# MIU60_REVE.net
KiCad netlist of a schematic drawn in EAGLE
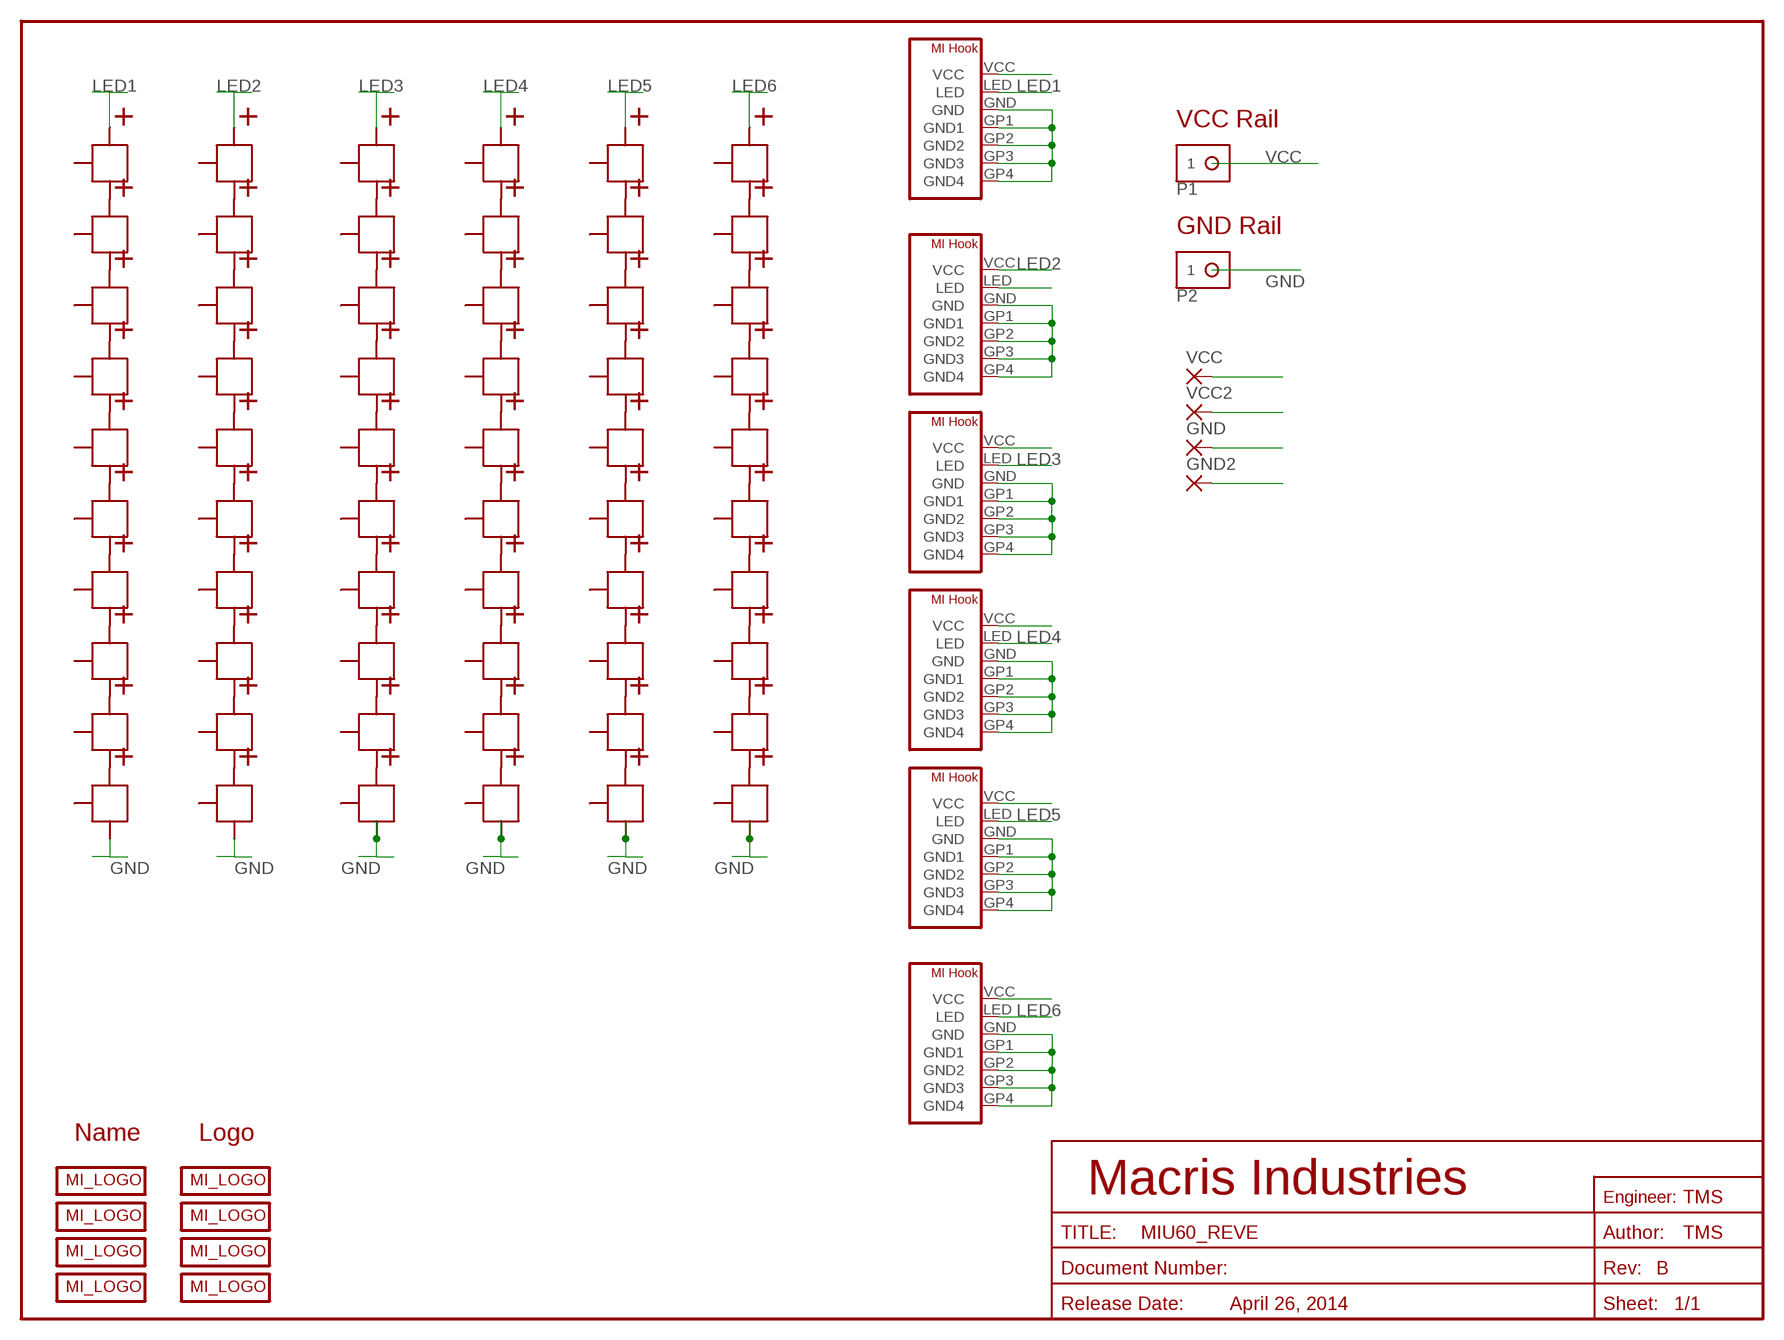
[diagram p0: schematic, sheet 1]

(export (version "E")
  (design (tool "Eeschema 10.0.6"))
  (components
    (comp (ref "GND")
      (value "SMD5")
      (footprint "eagle-import:SMD2,54-5,08")
      (libsource (lib "eagle-import") (part "SMD5"))
    )
    (comp (ref "GND2")
      (value "SMD5")
      (footprint "eagle-import:SMD2,54-5,08")
      (libsource (lib "eagle-import") (part "SMD5"))
    )
    (comp (ref "P1")
      (value "PAD-10G")
      (footprint "eagle-import:PAD_10G")
      (libsource (lib "eagle-import") (part "PAD-10G"))
    )
    (comp (ref "P2")
      (value "PAD-10G")
      (footprint "eagle-import:PAD_10G")
      (libsource (lib "eagle-import") (part "PAD-10G"))
    )
    (comp (ref "U$1")
      (value "MI_LOGO-50MIL")
      (footprint "eagle-import:MI_LOGO_NAME_2")
      (libsource (lib "eagle-import") (part "MI_LOGO-NAME_TWO"))
    )
    (comp (ref "U$2")
      (value "MI_LOGO-2014_USA")
      (footprint "eagle-import:MACRIS_USA_LOGO")
      (libsource (lib "eagle-import") (part "MI_LOGO-2014_USA"))
    )
    (comp (ref "U$3")
      (value "MI_LOGO-50MIL")
      (footprint "eagle-import:MI_LOGO_NAME_2")
      (libsource (lib "eagle-import") (part "MI_LOGO-NAME_TWO"))
    )
    (comp (ref "U$4")
      (value "MI_LOGO-2014_USA")
      (footprint "eagle-import:MACRIS_USA_LOGO")
      (libsource (lib "eagle-import") (part "MI_LOGO-2014_USA"))
    )
    (comp (ref "U$5")
      (value "MI_LOGO-50MIL")
      (footprint "eagle-import:MI_LOGO_NAME_2")
      (libsource (lib "eagle-import") (part "MI_LOGO-NAME_TWO"))
    )
    (comp (ref "U$6")
      (value "MI_LOGO-50MIL")
      (footprint "eagle-import:MI_LOGO_NAME_2")
      (libsource (lib "eagle-import") (part "MI_LOGO-NAME_TWO"))
    )
    (comp (ref "U$7")
      (value "MI_LOGO-2014_USA")
      (footprint "eagle-import:MACRIS_USA_LOGO")
      (libsource (lib "eagle-import") (part "MI_LOGO-2014_USA"))
    )
    (comp (ref "U$8")
      (value "MI_LOGO-2014_USA")
      (footprint "eagle-import:MACRIS_USA_LOGO")
      (libsource (lib "eagle-import") (part "MI_LOGO-2014_USA"))
    )
    (comp (ref "U$9")
      (value "MI_DRIVER_HOOKUP")
      (footprint "eagle-import:MI_DRIVE_HOOKUP")
      (libsource (lib "eagle-import") (part "MI_DRIVER_HOOKUP"))
    )
    (comp (ref "U$10")
      (value "MI_DRIVER_HOOKUP")
      (footprint "eagle-import:MI_DRIVE_HOOKUP")
      (libsource (lib "eagle-import") (part "MI_DRIVER_HOOKUP"))
    )
    (comp (ref "U$11")
      (value "MI_DRIVER_HOOKUP")
      (footprint "eagle-import:MI_DRIVE_HOOKUP")
      (libsource (lib "eagle-import") (part "MI_DRIVER_HOOKUP"))
    )
    (comp (ref "U$12")
      (value "MI_DRIVER_HOOKUP")
      (footprint "eagle-import:MI_DRIVE_HOOKUP")
      (libsource (lib "eagle-import") (part "MI_DRIVER_HOOKUP"))
    )
    (comp (ref "U$13")
      (value "MI_DRIVER_HOOKUP")
      (footprint "eagle-import:MI_DRIVE_HOOKUP")
      (libsource (lib "eagle-import") (part "MI_DRIVER_HOOKUP"))
    )
    (comp (ref "U$14")
      (value "MI_DRIVER_HOOKUP")
      (footprint "eagle-import:MI_DRIVE_HOOKUP")
      (libsource (lib "eagle-import") (part "MI_DRIVER_HOOKUP"))
    )
    (comp (ref "U$16")
      (value "CREE_XP")
      (footprint "eagle-import:XP")
      (libsource (lib "eagle-import") (part "CREE_XP"))
    )
    (comp (ref "U$17")
      (value "CREE_XP")
      (footprint "eagle-import:XP")
      (libsource (lib "eagle-import") (part "CREE_XP"))
    )
    (comp (ref "U$18")
      (value "CREE_XP")
      (footprint "eagle-import:XP")
      (libsource (lib "eagle-import") (part "CREE_XP"))
    )
    (comp (ref "U$19")
      (value "CREE_XP")
      (footprint "eagle-import:XP")
      (libsource (lib "eagle-import") (part "CREE_XP"))
    )
    (comp (ref "U$20")
      (value "CREE_XP")
      (footprint "eagle-import:XP")
      (libsource (lib "eagle-import") (part "CREE_XP"))
    )
    (comp (ref "U$21")
      (value "CREE_XP")
      (footprint "eagle-import:XP")
      (libsource (lib "eagle-import") (part "CREE_XP"))
    )
    (comp (ref "U$22")
      (value "CREE_XP")
      (footprint "eagle-import:XP")
      (libsource (lib "eagle-import") (part "CREE_XP"))
    )
    (comp (ref "U$23")
      (value "CREE_XP")
      (footprint "eagle-import:XP")
      (libsource (lib "eagle-import") (part "CREE_XP"))
    )
    (comp (ref "U$24")
      (value "CREE_XP")
      (footprint "eagle-import:XP")
      (libsource (lib "eagle-import") (part "CREE_XP"))
    )
    (comp (ref "U$25")
      (value "CREE_XP")
      (footprint "eagle-import:XP")
      (libsource (lib "eagle-import") (part "CREE_XP"))
    )
    (comp (ref "U$26")
      (value "CREE_XP")
      (footprint "eagle-import:XP")
      (libsource (lib "eagle-import") (part "CREE_XP"))
    )
    (comp (ref "U$27")
      (value "CREE_XP")
      (footprint "eagle-import:XP")
      (libsource (lib "eagle-import") (part "CREE_XP"))
    )
    (comp (ref "U$28")
      (value "CREE_XP")
      (footprint "eagle-import:XP")
      (libsource (lib "eagle-import") (part "CREE_XP"))
    )
    (comp (ref "U$29")
      (value "CREE_XP")
      (footprint "eagle-import:XP")
      (libsource (lib "eagle-import") (part "CREE_XP"))
    )
    (comp (ref "U$30")
      (value "CREE_XP")
      (footprint "eagle-import:XP")
      (libsource (lib "eagle-import") (part "CREE_XP"))
    )
    (comp (ref "U$31")
      (value "CREE_XP")
      (footprint "eagle-import:XP")
      (libsource (lib "eagle-import") (part "CREE_XP"))
    )
    (comp (ref "U$32")
      (value "CREE_XP")
      (footprint "eagle-import:XP")
      (libsource (lib "eagle-import") (part "CREE_XP"))
    )
    (comp (ref "U$33")
      (value "CREE_XP")
      (footprint "eagle-import:XP")
      (libsource (lib "eagle-import") (part "CREE_XP"))
    )
    (comp (ref "U$34")
      (value "CREE_XP")
      (footprint "eagle-import:XP")
      (libsource (lib "eagle-import") (part "CREE_XP"))
    )
    (comp (ref "U$35")
      (value "CREE_XP")
      (footprint "eagle-import:XP")
      (libsource (lib "eagle-import") (part "CREE_XP"))
    )
    (comp (ref "U$36")
      (value "CREE_XP")
      (footprint "eagle-import:XP")
      (libsource (lib "eagle-import") (part "CREE_XP"))
    )
    (comp (ref "U$37")
      (value "CREE_XP")
      (footprint "eagle-import:XP")
      (libsource (lib "eagle-import") (part "CREE_XP"))
    )
    (comp (ref "U$38")
      (value "CREE_XP")
      (footprint "eagle-import:XP")
      (libsource (lib "eagle-import") (part "CREE_XP"))
    )
    (comp (ref "U$39")
      (value "CREE_XP")
      (footprint "eagle-import:XP")
      (libsource (lib "eagle-import") (part "CREE_XP"))
    )
    (comp (ref "U$40")
      (value "CREE_XP")
      (footprint "eagle-import:XP")
      (libsource (lib "eagle-import") (part "CREE_XP"))
    )
    (comp (ref "U$41")
      (value "CREE_XP")
      (footprint "eagle-import:XP")
      (libsource (lib "eagle-import") (part "CREE_XP"))
    )
    (comp (ref "U$42")
      (value "CREE_XP")
      (footprint "eagle-import:XP")
      (libsource (lib "eagle-import") (part "CREE_XP"))
    )
    (comp (ref "U$43")
      (value "CREE_XP")
      (footprint "eagle-import:XP")
      (libsource (lib "eagle-import") (part "CREE_XP"))
    )
    (comp (ref "U$44")
      (value "CREE_XP")
      (footprint "eagle-import:XP")
      (libsource (lib "eagle-import") (part "CREE_XP"))
    )
    (comp (ref "U$45")
      (value "CREE_XP")
      (footprint "eagle-import:XP")
      (libsource (lib "eagle-import") (part "CREE_XP"))
    )
    (comp (ref "U$46")
      (value "CREE_XP")
      (footprint "eagle-import:XP")
      (libsource (lib "eagle-import") (part "CREE_XP"))
    )
    (comp (ref "U$47")
      (value "CREE_XP")
      (footprint "eagle-import:XP")
      (libsource (lib "eagle-import") (part "CREE_XP"))
    )
    (comp (ref "U$48")
      (value "CREE_XP")
      (footprint "eagle-import:XP")
      (libsource (lib "eagle-import") (part "CREE_XP"))
    )
    (comp (ref "U$49")
      (value "CREE_XP")
      (footprint "eagle-import:XP")
      (libsource (lib "eagle-import") (part "CREE_XP"))
    )
    (comp (ref "U$50")
      (value "CREE_XP")
      (footprint "eagle-import:XP")
      (libsource (lib "eagle-import") (part "CREE_XP"))
    )
    (comp (ref "U$51")
      (value "CREE_XP")
      (footprint "eagle-import:XP")
      (libsource (lib "eagle-import") (part "CREE_XP"))
    )
    (comp (ref "U$52")
      (value "CREE_XP")
      (footprint "eagle-import:XP")
      (libsource (lib "eagle-import") (part "CREE_XP"))
    )
    (comp (ref "U$53")
      (value "CREE_XP")
      (footprint "eagle-import:XP")
      (libsource (lib "eagle-import") (part "CREE_XP"))
    )
    (comp (ref "U$54")
      (value "CREE_XP")
      (footprint "eagle-import:XP")
      (libsource (lib "eagle-import") (part "CREE_XP"))
    )
    (comp (ref "U$55")
      (value "CREE_XP")
      (footprint "eagle-import:XP")
      (libsource (lib "eagle-import") (part "CREE_XP"))
    )
    (comp (ref "U$56")
      (value "CREE_XP")
      (footprint "eagle-import:XP")
      (libsource (lib "eagle-import") (part "CREE_XP"))
    )
    (comp (ref "U$57")
      (value "CREE_XP")
      (footprint "eagle-import:XP")
      (libsource (lib "eagle-import") (part "CREE_XP"))
    )
    (comp (ref "U$58")
      (value "CREE_XP")
      (footprint "eagle-import:XP")
      (libsource (lib "eagle-import") (part "CREE_XP"))
    )
    (comp (ref "U$59")
      (value "CREE_XP")
      (footprint "eagle-import:XP")
      (libsource (lib "eagle-import") (part "CREE_XP"))
    )
    (comp (ref "U$60")
      (value "CREE_XP")
      (footprint "eagle-import:XP")
      (libsource (lib "eagle-import") (part "CREE_XP"))
    )
    (comp (ref "U$61")
      (value "CREE_XP")
      (footprint "eagle-import:XP")
      (libsource (lib "eagle-import") (part "CREE_XP"))
    )
    (comp (ref "U$62")
      (value "CREE_XP")
      (footprint "eagle-import:XP")
      (libsource (lib "eagle-import") (part "CREE_XP"))
    )
    (comp (ref "U$63")
      (value "CREE_XP")
      (footprint "eagle-import:XP")
      (libsource (lib "eagle-import") (part "CREE_XP"))
    )
    (comp (ref "U$64")
      (value "CREE_XP")
      (footprint "eagle-import:XP")
      (libsource (lib "eagle-import") (part "CREE_XP"))
    )
    (comp (ref "U$65")
      (value "CREE_XP")
      (footprint "eagle-import:XP")
      (libsource (lib "eagle-import") (part "CREE_XP"))
    )
    (comp (ref "U$66")
      (value "CREE_XP")
      (footprint "eagle-import:XP")
      (libsource (lib "eagle-import") (part "CREE_XP"))
    )
    (comp (ref "U$67")
      (value "CREE_XP")
      (footprint "eagle-import:XP")
      (libsource (lib "eagle-import") (part "CREE_XP"))
    )
    (comp (ref "U$68")
      (value "CREE_XP")
      (footprint "eagle-import:XP")
      (libsource (lib "eagle-import") (part "CREE_XP"))
    )
    (comp (ref "U$69")
      (value "CREE_XP")
      (footprint "eagle-import:XP")
      (libsource (lib "eagle-import") (part "CREE_XP"))
    )
    (comp (ref "U$70")
      (value "CREE_XP")
      (footprint "eagle-import:XP")
      (libsource (lib "eagle-import") (part "CREE_XP"))
    )
    (comp (ref "U$71")
      (value "CREE_XP")
      (footprint "eagle-import:XP")
      (libsource (lib "eagle-import") (part "CREE_XP"))
    )
    (comp (ref "U$72")
      (value "CREE_XP")
      (footprint "eagle-import:XP")
      (libsource (lib "eagle-import") (part "CREE_XP"))
    )
    (comp (ref "U$73")
      (value "CREE_XP")
      (footprint "eagle-import:XP")
      (libsource (lib "eagle-import") (part "CREE_XP"))
    )
    (comp (ref "U$74")
      (value "CREE_XP")
      (footprint "eagle-import:XP")
      (libsource (lib "eagle-import") (part "CREE_XP"))
    )
    (comp (ref "U$75")
      (value "CREE_XP")
      (footprint "eagle-import:XP")
      (libsource (lib "eagle-import") (part "CREE_XP"))
    )
    (comp (ref "VCC")
      (value "SMD5")
      (footprint "eagle-import:SMD2,54-5,08")
      (libsource (lib "eagle-import") (part "SMD5"))
    )
    (comp (ref "VCC2")
      (value "SMD5")
      (footprint "eagle-import:SMD2,54-5,08")
      (libsource (lib "eagle-import") (part "SMD5"))
    )
  )
  (nets
    (net (code "1") (name "/GND") (class "Default")
      (node (ref "GND") (pin "1") (pinfunction "P_1") (pintype "passive"))
      (node (ref "GND2") (pin "1") (pinfunction "P_1") (pintype "passive"))
      (node (ref "P2") (pin "1") (pinfunction "1_1") (pintype "passive"))
      (node (ref "U$10") (pin "GND") (pinfunction "GND_GND") (pintype "bidirectional"))
      (node (ref "U$10") (pin "GP1") (pinfunction "GND1_GP1") (pintype "bidirectional"))
      (node (ref "U$10") (pin "GP2") (pinfunction "GND2_GP2") (pintype "bidirectional"))
      (node (ref "U$10") (pin "GP3") (pinfunction "GND3_GP3") (pintype "bidirectional"))
      (node (ref "U$10") (pin "GP4") (pinfunction "GND4_GP4") (pintype "bidirectional"))
      (node (ref "U$11") (pin "GND") (pinfunction "GND_GND") (pintype "bidirectional"))
      (node (ref "U$11") (pin "GP1") (pinfunction "GND1_GP1") (pintype "bidirectional"))
      (node (ref "U$11") (pin "GP2") (pinfunction "GND2_GP2") (pintype "bidirectional"))
      (node (ref "U$11") (pin "GP3") (pinfunction "GND3_GP3") (pintype "bidirectional"))
      (node (ref "U$11") (pin "GP4") (pinfunction "GND4_GP4") (pintype "bidirectional"))
      (node (ref "U$12") (pin "GND") (pinfunction "GND_GND") (pintype "bidirectional"))
      (node (ref "U$12") (pin "GP1") (pinfunction "GND1_GP1") (pintype "bidirectional"))
      (node (ref "U$12") (pin "GP2") (pinfunction "GND2_GP2") (pintype "bidirectional"))
      (node (ref "U$12") (pin "GP3") (pinfunction "GND3_GP3") (pintype "bidirectional"))
      (node (ref "U$12") (pin "GP4") (pinfunction "GND4_GP4") (pintype "bidirectional"))
      (node (ref "U$13") (pin "GND") (pinfunction "GND_GND") (pintype "bidirectional"))
      (node (ref "U$13") (pin "GP1") (pinfunction "GND1_GP1") (pintype "bidirectional"))
      (node (ref "U$13") (pin "GP2") (pinfunction "GND2_GP2") (pintype "bidirectional"))
      (node (ref "U$13") (pin "GP3") (pinfunction "GND3_GP3") (pintype "bidirectional"))
      (node (ref "U$13") (pin "GP4") (pinfunction "GND4_GP4") (pintype "bidirectional"))
      (node (ref "U$14") (pin "GND") (pinfunction "GND_GND") (pintype "bidirectional"))
      (node (ref "U$14") (pin "GP1") (pinfunction "GND1_GP1") (pintype "bidirectional"))
      (node (ref "U$14") (pin "GP2") (pinfunction "GND2_GP2") (pintype "bidirectional"))
      (node (ref "U$14") (pin "GP3") (pinfunction "GND3_GP3") (pintype "bidirectional"))
      (node (ref "U$14") (pin "GP4") (pinfunction "GND4_GP4") (pintype "bidirectional"))
      (node (ref "U$25") (pin "NEGATIVE") (pinfunction "NEGATIVE_NEGATIVE") (pintype "bidirectional"))
      (node (ref "U$25") (pin "NEGATIVE1") (pinfunction "NEGATIVE_NEGATIVE1") (pintype "bidirectional"))
      (node (ref "U$35") (pin "NEGATIVE") (pinfunction "NEGATIVE_NEGATIVE") (pintype "bidirectional"))
      (node (ref "U$35") (pin "NEGATIVE1") (pinfunction "NEGATIVE_NEGATIVE1") (pintype "bidirectional"))
      (node (ref "U$45") (pin "NEGATIVE") (pinfunction "NEGATIVE_NEGATIVE") (pintype "bidirectional"))
      (node (ref "U$45") (pin "NEGATIVE1") (pinfunction "NEGATIVE_NEGATIVE1") (pintype "bidirectional"))
      (node (ref "U$55") (pin "NEGATIVE") (pinfunction "NEGATIVE_NEGATIVE") (pintype "bidirectional"))
      (node (ref "U$55") (pin "NEGATIVE1") (pinfunction "NEGATIVE_NEGATIVE1") (pintype "bidirectional"))
      (node (ref "U$65") (pin "NEGATIVE") (pinfunction "NEGATIVE_NEGATIVE") (pintype "bidirectional"))
      (node (ref "U$65") (pin "NEGATIVE1") (pinfunction "NEGATIVE_NEGATIVE1") (pintype "bidirectional"))
      (node (ref "U$75") (pin "NEGATIVE") (pinfunction "NEGATIVE_NEGATIVE") (pintype "bidirectional"))
      (node (ref "U$75") (pin "NEGATIVE1") (pinfunction "NEGATIVE_NEGATIVE1") (pintype "bidirectional"))
      (node (ref "U$9") (pin "GND") (pinfunction "GND_GND") (pintype "bidirectional"))
      (node (ref "U$9") (pin "GP1") (pinfunction "GND1_GP1") (pintype "bidirectional"))
      (node (ref "U$9") (pin "GP2") (pinfunction "GND2_GP2") (pintype "bidirectional"))
      (node (ref "U$9") (pin "GP3") (pinfunction "GND3_GP3") (pintype "bidirectional"))
      (node (ref "U$9") (pin "GP4") (pinfunction "GND4_GP4") (pintype "bidirectional"))
    )
    (net (code "2") (name "/LED1") (class "Default")
      (node (ref "U$16") (pin "POSITIVE") (pinfunction "POSITIVE_POSITIVE") (pintype "bidirectional"))
      (node (ref "U$16") (pin "POSITIVE1") (pinfunction "POSITIVE_POSITIVE1") (pintype "bidirectional"))
      (node (ref "U$9") (pin "LED") (pinfunction "LED_LED") (pintype "bidirectional"))
    )
    (net (code "3") (name "/LED2") (class "Default")
      (node (ref "U$10") (pin "LED") (pinfunction "LED_LED") (pintype "bidirectional"))
      (node (ref "U$26") (pin "POSITIVE") (pinfunction "POSITIVE_POSITIVE") (pintype "bidirectional"))
      (node (ref "U$26") (pin "POSITIVE1") (pinfunction "POSITIVE_POSITIVE1") (pintype "bidirectional"))
    )
    (net (code "4") (name "/LED3") (class "Default")
      (node (ref "U$11") (pin "LED") (pinfunction "LED_LED") (pintype "bidirectional"))
      (node (ref "U$36") (pin "POSITIVE") (pinfunction "POSITIVE_POSITIVE") (pintype "bidirectional"))
      (node (ref "U$36") (pin "POSITIVE1") (pinfunction "POSITIVE_POSITIVE1") (pintype "bidirectional"))
    )
    (net (code "5") (name "/LED4") (class "Default")
      (node (ref "U$12") (pin "LED") (pinfunction "LED_LED") (pintype "bidirectional"))
      (node (ref "U$46") (pin "POSITIVE") (pinfunction "POSITIVE_POSITIVE") (pintype "bidirectional"))
      (node (ref "U$46") (pin "POSITIVE1") (pinfunction "POSITIVE_POSITIVE1") (pintype "bidirectional"))
    )
    (net (code "6") (name "/LED5") (class "Default")
      (node (ref "U$13") (pin "LED") (pinfunction "LED_LED") (pintype "bidirectional"))
      (node (ref "U$56") (pin "POSITIVE") (pinfunction "POSITIVE_POSITIVE") (pintype "bidirectional"))
      (node (ref "U$56") (pin "POSITIVE1") (pinfunction "POSITIVE_POSITIVE1") (pintype "bidirectional"))
    )
    (net (code "7") (name "/LED6") (class "Default")
      (node (ref "U$14") (pin "LED") (pinfunction "LED_LED") (pintype "bidirectional"))
      (node (ref "U$66") (pin "POSITIVE") (pinfunction "POSITIVE_POSITIVE") (pintype "bidirectional"))
      (node (ref "U$66") (pin "POSITIVE1") (pinfunction "POSITIVE_POSITIVE1") (pintype "bidirectional"))
    )
    (net (code "8") (name "/VCC") (class "Default")
      (node (ref "P1") (pin "1") (pinfunction "1_1") (pintype "passive"))
      (node (ref "U$10") (pin "VCC") (pinfunction "VCC_VCC") (pintype "bidirectional"))
      (node (ref "U$11") (pin "VCC") (pinfunction "VCC_VCC") (pintype "bidirectional"))
      (node (ref "U$12") (pin "VCC") (pinfunction "VCC_VCC") (pintype "bidirectional"))
      (node (ref "U$13") (pin "VCC") (pinfunction "VCC_VCC") (pintype "bidirectional"))
      (node (ref "U$14") (pin "VCC") (pinfunction "VCC_VCC") (pintype "bidirectional"))
      (node (ref "U$9") (pin "VCC") (pinfunction "VCC_VCC") (pintype "bidirectional"))
      (node (ref "VCC") (pin "1") (pinfunction "P_1") (pintype "passive"))
      (node (ref "VCC2") (pin "1") (pinfunction "P_1") (pintype "passive"))
    )
    (net (code "9") (name "Net-(U$16-NEGATIVE-PadNEGATIVE1)") (class "Default")
      (node (ref "U$16") (pin "NEGATIVE") (pinfunction "NEGATIVE_NEGATIVE") (pintype "bidirectional"))
      (node (ref "U$16") (pin "NEGATIVE1") (pinfunction "NEGATIVE_NEGATIVE1") (pintype "bidirectional"))
      (node (ref "U$17") (pin "POSITIVE") (pinfunction "POSITIVE_POSITIVE") (pintype "bidirectional"))
      (node (ref "U$17") (pin "POSITIVE1") (pinfunction "POSITIVE_POSITIVE1") (pintype "bidirectional"))
    )
    (net (code "10") (name "Net-(U$17-NEGATIVE-PadNEGATIVE1)") (class "Default")
      (node (ref "U$17") (pin "NEGATIVE") (pinfunction "NEGATIVE_NEGATIVE") (pintype "bidirectional"))
      (node (ref "U$17") (pin "NEGATIVE1") (pinfunction "NEGATIVE_NEGATIVE1") (pintype "bidirectional"))
      (node (ref "U$18") (pin "POSITIVE") (pinfunction "POSITIVE_POSITIVE") (pintype "bidirectional"))
      (node (ref "U$18") (pin "POSITIVE1") (pinfunction "POSITIVE_POSITIVE1") (pintype "bidirectional"))
    )
    (net (code "11") (name "Net-(U$18-NEGATIVE-PadNEGATIVE1)") (class "Default")
      (node (ref "U$18") (pin "NEGATIVE") (pinfunction "NEGATIVE_NEGATIVE") (pintype "bidirectional"))
      (node (ref "U$18") (pin "NEGATIVE1") (pinfunction "NEGATIVE_NEGATIVE1") (pintype "bidirectional"))
      (node (ref "U$19") (pin "POSITIVE") (pinfunction "POSITIVE_POSITIVE") (pintype "bidirectional"))
      (node (ref "U$19") (pin "POSITIVE1") (pinfunction "POSITIVE_POSITIVE1") (pintype "bidirectional"))
    )
    (net (code "12") (name "Net-(U$19-NEGATIVE-PadNEGATIVE1)") (class "Default")
      (node (ref "U$19") (pin "NEGATIVE") (pinfunction "NEGATIVE_NEGATIVE") (pintype "bidirectional"))
      (node (ref "U$19") (pin "NEGATIVE1") (pinfunction "NEGATIVE_NEGATIVE1") (pintype "bidirectional"))
      (node (ref "U$20") (pin "POSITIVE") (pinfunction "POSITIVE_POSITIVE") (pintype "bidirectional"))
      (node (ref "U$20") (pin "POSITIVE1") (pinfunction "POSITIVE_POSITIVE1") (pintype "bidirectional"))
    )
    (net (code "13") (name "Net-(U$20-NEGATIVE-PadNEGATIVE1)") (class "Default")
      (node (ref "U$20") (pin "NEGATIVE") (pinfunction "NEGATIVE_NEGATIVE") (pintype "bidirectional"))
      (node (ref "U$20") (pin "NEGATIVE1") (pinfunction "NEGATIVE_NEGATIVE1") (pintype "bidirectional"))
      (node (ref "U$21") (pin "POSITIVE") (pinfunction "POSITIVE_POSITIVE") (pintype "bidirectional"))
      (node (ref "U$21") (pin "POSITIVE1") (pinfunction "POSITIVE_POSITIVE1") (pintype "bidirectional"))
    )
    (net (code "14") (name "Net-(U$21-NEGATIVE-PadNEGATIVE1)") (class "Default")
      (node (ref "U$21") (pin "NEGATIVE") (pinfunction "NEGATIVE_NEGATIVE") (pintype "bidirectional"))
      (node (ref "U$21") (pin "NEGATIVE1") (pinfunction "NEGATIVE_NEGATIVE1") (pintype "bidirectional"))
      (node (ref "U$22") (pin "POSITIVE") (pinfunction "POSITIVE_POSITIVE") (pintype "bidirectional"))
      (node (ref "U$22") (pin "POSITIVE1") (pinfunction "POSITIVE_POSITIVE1") (pintype "bidirectional"))
    )
    (net (code "15") (name "Net-(U$22-NEGATIVE-PadNEGATIVE1)") (class "Default")
      (node (ref "U$22") (pin "NEGATIVE") (pinfunction "NEGATIVE_NEGATIVE") (pintype "bidirectional"))
      (node (ref "U$22") (pin "NEGATIVE1") (pinfunction "NEGATIVE_NEGATIVE1") (pintype "bidirectional"))
      (node (ref "U$23") (pin "POSITIVE") (pinfunction "POSITIVE_POSITIVE") (pintype "bidirectional"))
      (node (ref "U$23") (pin "POSITIVE1") (pinfunction "POSITIVE_POSITIVE1") (pintype "bidirectional"))
    )
    (net (code "16") (name "Net-(U$23-NEGATIVE-PadNEGATIVE1)") (class "Default")
      (node (ref "U$23") (pin "NEGATIVE") (pinfunction "NEGATIVE_NEGATIVE") (pintype "bidirectional"))
      (node (ref "U$23") (pin "NEGATIVE1") (pinfunction "NEGATIVE_NEGATIVE1") (pintype "bidirectional"))
      (node (ref "U$24") (pin "POSITIVE") (pinfunction "POSITIVE_POSITIVE") (pintype "bidirectional"))
      (node (ref "U$24") (pin "POSITIVE1") (pinfunction "POSITIVE_POSITIVE1") (pintype "bidirectional"))
    )
    (net (code "17") (name "Net-(U$24-NEGATIVE-PadNEGATIVE1)") (class "Default")
      (node (ref "U$24") (pin "NEGATIVE") (pinfunction "NEGATIVE_NEGATIVE") (pintype "bidirectional"))
      (node (ref "U$24") (pin "NEGATIVE1") (pinfunction "NEGATIVE_NEGATIVE1") (pintype "bidirectional"))
      (node (ref "U$25") (pin "POSITIVE") (pinfunction "POSITIVE_POSITIVE") (pintype "bidirectional"))
      (node (ref "U$25") (pin "POSITIVE1") (pinfunction "POSITIVE_POSITIVE1") (pintype "bidirectional"))
    )
    (net (code "18") (name "Net-(U$26-NEGATIVE-PadNEGATIVE1)") (class "Default")
      (node (ref "U$26") (pin "NEGATIVE") (pinfunction "NEGATIVE_NEGATIVE") (pintype "bidirectional"))
      (node (ref "U$26") (pin "NEGATIVE1") (pinfunction "NEGATIVE_NEGATIVE1") (pintype "bidirectional"))
      (node (ref "U$27") (pin "POSITIVE") (pinfunction "POSITIVE_POSITIVE") (pintype "bidirectional"))
      (node (ref "U$27") (pin "POSITIVE1") (pinfunction "POSITIVE_POSITIVE1") (pintype "bidirectional"))
    )
    (net (code "19") (name "Net-(U$27-NEGATIVE-PadNEGATIVE1)") (class "Default")
      (node (ref "U$27") (pin "NEGATIVE") (pinfunction "NEGATIVE_NEGATIVE") (pintype "bidirectional"))
      (node (ref "U$27") (pin "NEGATIVE1") (pinfunction "NEGATIVE_NEGATIVE1") (pintype "bidirectional"))
      (node (ref "U$28") (pin "POSITIVE") (pinfunction "POSITIVE_POSITIVE") (pintype "bidirectional"))
      (node (ref "U$28") (pin "POSITIVE1") (pinfunction "POSITIVE_POSITIVE1") (pintype "bidirectional"))
    )
    (net (code "20") (name "Net-(U$28-NEGATIVE-PadNEGATIVE1)") (class "Default")
      (node (ref "U$28") (pin "NEGATIVE") (pinfunction "NEGATIVE_NEGATIVE") (pintype "bidirectional"))
      (node (ref "U$28") (pin "NEGATIVE1") (pinfunction "NEGATIVE_NEGATIVE1") (pintype "bidirectional"))
      (node (ref "U$29") (pin "POSITIVE") (pinfunction "POSITIVE_POSITIVE") (pintype "bidirectional"))
      (node (ref "U$29") (pin "POSITIVE1") (pinfunction "POSITIVE_POSITIVE1") (pintype "bidirectional"))
    )
    (net (code "21") (name "Net-(U$29-NEGATIVE-PadNEGATIVE1)") (class "Default")
      (node (ref "U$29") (pin "NEGATIVE") (pinfunction "NEGATIVE_NEGATIVE") (pintype "bidirectional"))
      (node (ref "U$29") (pin "NEGATIVE1") (pinfunction "NEGATIVE_NEGATIVE1") (pintype "bidirectional"))
      (node (ref "U$30") (pin "POSITIVE") (pinfunction "POSITIVE_POSITIVE") (pintype "bidirectional"))
      (node (ref "U$30") (pin "POSITIVE1") (pinfunction "POSITIVE_POSITIVE1") (pintype "bidirectional"))
    )
    (net (code "22") (name "Net-(U$30-NEGATIVE-PadNEGATIVE1)") (class "Default")
      (node (ref "U$30") (pin "NEGATIVE") (pinfunction "NEGATIVE_NEGATIVE") (pintype "bidirectional"))
      (node (ref "U$30") (pin "NEGATIVE1") (pinfunction "NEGATIVE_NEGATIVE1") (pintype "bidirectional"))
      (node (ref "U$31") (pin "POSITIVE") (pinfunction "POSITIVE_POSITIVE") (pintype "bidirectional"))
      (node (ref "U$31") (pin "POSITIVE1") (pinfunction "POSITIVE_POSITIVE1") (pintype "bidirectional"))
    )
    (net (code "23") (name "Net-(U$31-NEGATIVE-PadNEGATIVE1)") (class "Default")
      (node (ref "U$31") (pin "NEGATIVE") (pinfunction "NEGATIVE_NEGATIVE") (pintype "bidirectional"))
      (node (ref "U$31") (pin "NEGATIVE1") (pinfunction "NEGATIVE_NEGATIVE1") (pintype "bidirectional"))
      (node (ref "U$32") (pin "POSITIVE") (pinfunction "POSITIVE_POSITIVE") (pintype "bidirectional"))
      (node (ref "U$32") (pin "POSITIVE1") (pinfunction "POSITIVE_POSITIVE1") (pintype "bidirectional"))
    )
    (net (code "24") (name "Net-(U$32-NEGATIVE-PadNEGATIVE1)") (class "Default")
      (node (ref "U$32") (pin "NEGATIVE") (pinfunction "NEGATIVE_NEGATIVE") (pintype "bidirectional"))
      (node (ref "U$32") (pin "NEGATIVE1") (pinfunction "NEGATIVE_NEGATIVE1") (pintype "bidirectional"))
      (node (ref "U$33") (pin "POSITIVE") (pinfunction "POSITIVE_POSITIVE") (pintype "bidirectional"))
      (node (ref "U$33") (pin "POSITIVE1") (pinfunction "POSITIVE_POSITIVE1") (pintype "bidirectional"))
    )
    (net (code "25") (name "Net-(U$33-NEGATIVE-PadNEGATIVE1)") (class "Default")
      (node (ref "U$33") (pin "NEGATIVE") (pinfunction "NEGATIVE_NEGATIVE") (pintype "bidirectional"))
      (node (ref "U$33") (pin "NEGATIVE1") (pinfunction "NEGATIVE_NEGATIVE1") (pintype "bidirectional"))
      (node (ref "U$34") (pin "POSITIVE") (pinfunction "POSITIVE_POSITIVE") (pintype "bidirectional"))
      (node (ref "U$34") (pin "POSITIVE1") (pinfunction "POSITIVE_POSITIVE1") (pintype "bidirectional"))
    )
    (net (code "26") (name "Net-(U$34-NEGATIVE-PadNEGATIVE1)") (class "Default")
      (node (ref "U$34") (pin "NEGATIVE") (pinfunction "NEGATIVE_NEGATIVE") (pintype "bidirectional"))
      (node (ref "U$34") (pin "NEGATIVE1") (pinfunction "NEGATIVE_NEGATIVE1") (pintype "bidirectional"))
      (node (ref "U$35") (pin "POSITIVE") (pinfunction "POSITIVE_POSITIVE") (pintype "bidirectional"))
      (node (ref "U$35") (pin "POSITIVE1") (pinfunction "POSITIVE_POSITIVE1") (pintype "bidirectional"))
    )
    (net (code "27") (name "Net-(U$36-NEGATIVE-PadNEGATIVE1)") (class "Default")
      (node (ref "U$36") (pin "NEGATIVE") (pinfunction "NEGATIVE_NEGATIVE") (pintype "bidirectional"))
      (node (ref "U$36") (pin "NEGATIVE1") (pinfunction "NEGATIVE_NEGATIVE1") (pintype "bidirectional"))
      (node (ref "U$37") (pin "POSITIVE") (pinfunction "POSITIVE_POSITIVE") (pintype "bidirectional"))
      (node (ref "U$37") (pin "POSITIVE1") (pinfunction "POSITIVE_POSITIVE1") (pintype "bidirectional"))
    )
    (net (code "28") (name "Net-(U$37-NEGATIVE-PadNEGATIVE1)") (class "Default")
      (node (ref "U$37") (pin "NEGATIVE") (pinfunction "NEGATIVE_NEGATIVE") (pintype "bidirectional"))
      (node (ref "U$37") (pin "NEGATIVE1") (pinfunction "NEGATIVE_NEGATIVE1") (pintype "bidirectional"))
      (node (ref "U$38") (pin "POSITIVE") (pinfunction "POSITIVE_POSITIVE") (pintype "bidirectional"))
      (node (ref "U$38") (pin "POSITIVE1") (pinfunction "POSITIVE_POSITIVE1") (pintype "bidirectional"))
    )
    (net (code "29") (name "Net-(U$38-NEGATIVE-PadNEGATIVE1)") (class "Default")
      (node (ref "U$38") (pin "NEGATIVE") (pinfunction "NEGATIVE_NEGATIVE") (pintype "bidirectional"))
      (node (ref "U$38") (pin "NEGATIVE1") (pinfunction "NEGATIVE_NEGATIVE1") (pintype "bidirectional"))
      (node (ref "U$39") (pin "POSITIVE") (pinfunction "POSITIVE_POSITIVE") (pintype "bidirectional"))
      (node (ref "U$39") (pin "POSITIVE1") (pinfunction "POSITIVE_POSITIVE1") (pintype "bidirectional"))
    )
    (net (code "30") (name "Net-(U$39-NEGATIVE-PadNEGATIVE1)") (class "Default")
      (node (ref "U$39") (pin "NEGATIVE") (pinfunction "NEGATIVE_NEGATIVE") (pintype "bidirectional"))
      (node (ref "U$39") (pin "NEGATIVE1") (pinfunction "NEGATIVE_NEGATIVE1") (pintype "bidirectional"))
      (node (ref "U$40") (pin "POSITIVE") (pinfunction "POSITIVE_POSITIVE") (pintype "bidirectional"))
      (node (ref "U$40") (pin "POSITIVE1") (pinfunction "POSITIVE_POSITIVE1") (pintype "bidirectional"))
    )
    (net (code "31") (name "Net-(U$40-NEGATIVE-PadNEGATIVE1)") (class "Default")
      (node (ref "U$40") (pin "NEGATIVE") (pinfunction "NEGATIVE_NEGATIVE") (pintype "bidirectional"))
      (node (ref "U$40") (pin "NEGATIVE1") (pinfunction "NEGATIVE_NEGATIVE1") (pintype "bidirectional"))
      (node (ref "U$41") (pin "POSITIVE") (pinfunction "POSITIVE_POSITIVE") (pintype "bidirectional"))
      (node (ref "U$41") (pin "POSITIVE1") (pinfunction "POSITIVE_POSITIVE1") (pintype "bidirectional"))
    )
    (net (code "32") (name "Net-(U$41-NEGATIVE-PadNEGATIVE1)") (class "Default")
      (node (ref "U$41") (pin "NEGATIVE") (pinfunction "NEGATIVE_NEGATIVE") (pintype "bidirectional"))
      (node (ref "U$41") (pin "NEGATIVE1") (pinfunction "NEGATIVE_NEGATIVE1") (pintype "bidirectional"))
      (node (ref "U$42") (pin "POSITIVE") (pinfunction "POSITIVE_POSITIVE") (pintype "bidirectional"))
      (node (ref "U$42") (pin "POSITIVE1") (pinfunction "POSITIVE_POSITIVE1") (pintype "bidirectional"))
    )
    (net (code "33") (name "Net-(U$42-NEGATIVE-PadNEGATIVE1)") (class "Default")
      (node (ref "U$42") (pin "NEGATIVE") (pinfunction "NEGATIVE_NEGATIVE") (pintype "bidirectional"))
      (node (ref "U$42") (pin "NEGATIVE1") (pinfunction "NEGATIVE_NEGATIVE1") (pintype "bidirectional"))
      (node (ref "U$43") (pin "POSITIVE") (pinfunction "POSITIVE_POSITIVE") (pintype "bidirectional"))
      (node (ref "U$43") (pin "POSITIVE1") (pinfunction "POSITIVE_POSITIVE1") (pintype "bidirectional"))
    )
    (net (code "34") (name "Net-(U$43-NEGATIVE-PadNEGATIVE1)") (class "Default")
      (node (ref "U$43") (pin "NEGATIVE") (pinfunction "NEGATIVE_NEGATIVE") (pintype "bidirectional"))
      (node (ref "U$43") (pin "NEGATIVE1") (pinfunction "NEGATIVE_NEGATIVE1") (pintype "bidirectional"))
      (node (ref "U$44") (pin "POSITIVE") (pinfunction "POSITIVE_POSITIVE") (pintype "bidirectional"))
      (node (ref "U$44") (pin "POSITIVE1") (pinfunction "POSITIVE_POSITIVE1") (pintype "bidirectional"))
    )
    (net (code "35") (name "Net-(U$44-NEGATIVE-PadNEGATIVE1)") (class "Default")
      (node (ref "U$44") (pin "NEGATIVE") (pinfunction "NEGATIVE_NEGATIVE") (pintype "bidirectional"))
      (node (ref "U$44") (pin "NEGATIVE1") (pinfunction "NEGATIVE_NEGATIVE1") (pintype "bidirectional"))
      (node (ref "U$45") (pin "POSITIVE") (pinfunction "POSITIVE_POSITIVE") (pintype "bidirectional"))
      (node (ref "U$45") (pin "POSITIVE1") (pinfunction "POSITIVE_POSITIVE1") (pintype "bidirectional"))
    )
    (net (code "36") (name "Net-(U$46-NEGATIVE-PadNEGATIVE1)") (class "Default")
      (node (ref "U$46") (pin "NEGATIVE") (pinfunction "NEGATIVE_NEGATIVE") (pintype "bidirectional"))
      (node (ref "U$46") (pin "NEGATIVE1") (pinfunction "NEGATIVE_NEGATIVE1") (pintype "bidirectional"))
      (node (ref "U$47") (pin "POSITIVE") (pinfunction "POSITIVE_POSITIVE") (pintype "bidirectional"))
      (node (ref "U$47") (pin "POSITIVE1") (pinfunction "POSITIVE_POSITIVE1") (pintype "bidirectional"))
    )
    (net (code "37") (name "Net-(U$47-NEGATIVE-PadNEGATIVE1)") (class "Default")
      (node (ref "U$47") (pin "NEGATIVE") (pinfunction "NEGATIVE_NEGATIVE") (pintype "bidirectional"))
      (node (ref "U$47") (pin "NEGATIVE1") (pinfunction "NEGATIVE_NEGATIVE1") (pintype "bidirectional"))
      (node (ref "U$48") (pin "POSITIVE") (pinfunction "POSITIVE_POSITIVE") (pintype "bidirectional"))
      (node (ref "U$48") (pin "POSITIVE1") (pinfunction "POSITIVE_POSITIVE1") (pintype "bidirectional"))
    )
    (net (code "38") (name "Net-(U$48-NEGATIVE-PadNEGATIVE1)") (class "Default")
      (node (ref "U$48") (pin "NEGATIVE") (pinfunction "NEGATIVE_NEGATIVE") (pintype "bidirectional"))
      (node (ref "U$48") (pin "NEGATIVE1") (pinfunction "NEGATIVE_NEGATIVE1") (pintype "bidirectional"))
      (node (ref "U$49") (pin "POSITIVE") (pinfunction "POSITIVE_POSITIVE") (pintype "bidirectional"))
      (node (ref "U$49") (pin "POSITIVE1") (pinfunction "POSITIVE_POSITIVE1") (pintype "bidirectional"))
    )
    (net (code "39") (name "Net-(U$49-NEGATIVE-PadNEGATIVE1)") (class "Default")
      (node (ref "U$49") (pin "NEGATIVE") (pinfunction "NEGATIVE_NEGATIVE") (pintype "bidirectional"))
      (node (ref "U$49") (pin "NEGATIVE1") (pinfunction "NEGATIVE_NEGATIVE1") (pintype "bidirectional"))
      (node (ref "U$50") (pin "POSITIVE") (pinfunction "POSITIVE_POSITIVE") (pintype "bidirectional"))
      (node (ref "U$50") (pin "POSITIVE1") (pinfunction "POSITIVE_POSITIVE1") (pintype "bidirectional"))
    )
    (net (code "40") (name "Net-(U$50-NEGATIVE-PadNEGATIVE1)") (class "Default")
      (node (ref "U$50") (pin "NEGATIVE") (pinfunction "NEGATIVE_NEGATIVE") (pintype "bidirectional"))
      (node (ref "U$50") (pin "NEGATIVE1") (pinfunction "NEGATIVE_NEGATIVE1") (pintype "bidirectional"))
      (node (ref "U$51") (pin "POSITIVE") (pinfunction "POSITIVE_POSITIVE") (pintype "bidirectional"))
      (node (ref "U$51") (pin "POSITIVE1") (pinfunction "POSITIVE_POSITIVE1") (pintype "bidirectional"))
    )
    (net (code "41") (name "Net-(U$51-NEGATIVE-PadNEGATIVE1)") (class "Default")
      (node (ref "U$51") (pin "NEGATIVE") (pinfunction "NEGATIVE_NEGATIVE") (pintype "bidirectional"))
      (node (ref "U$51") (pin "NEGATIVE1") (pinfunction "NEGATIVE_NEGATIVE1") (pintype "bidirectional"))
      (node (ref "U$52") (pin "POSITIVE") (pinfunction "POSITIVE_POSITIVE") (pintype "bidirectional"))
      (node (ref "U$52") (pin "POSITIVE1") (pinfunction "POSITIVE_POSITIVE1") (pintype "bidirectional"))
    )
    (net (code "42") (name "Net-(U$52-NEGATIVE-PadNEGATIVE1)") (class "Default")
      (node (ref "U$52") (pin "NEGATIVE") (pinfunction "NEGATIVE_NEGATIVE") (pintype "bidirectional"))
      (node (ref "U$52") (pin "NEGATIVE1") (pinfunction "NEGATIVE_NEGATIVE1") (pintype "bidirectional"))
      (node (ref "U$53") (pin "POSITIVE") (pinfunction "POSITIVE_POSITIVE") (pintype "bidirectional"))
      (node (ref "U$53") (pin "POSITIVE1") (pinfunction "POSITIVE_POSITIVE1") (pintype "bidirectional"))
    )
    (net (code "43") (name "Net-(U$53-NEGATIVE-PadNEGATIVE1)") (class "Default")
      (node (ref "U$53") (pin "NEGATIVE") (pinfunction "NEGATIVE_NEGATIVE") (pintype "bidirectional"))
      (node (ref "U$53") (pin "NEGATIVE1") (pinfunction "NEGATIVE_NEGATIVE1") (pintype "bidirectional"))
      (node (ref "U$54") (pin "POSITIVE") (pinfunction "POSITIVE_POSITIVE") (pintype "bidirectional"))
      (node (ref "U$54") (pin "POSITIVE1") (pinfunction "POSITIVE_POSITIVE1") (pintype "bidirectional"))
    )
    (net (code "44") (name "Net-(U$54-NEGATIVE-PadNEGATIVE1)") (class "Default")
      (node (ref "U$54") (pin "NEGATIVE") (pinfunction "NEGATIVE_NEGATIVE") (pintype "bidirectional"))
      (node (ref "U$54") (pin "NEGATIVE1") (pinfunction "NEGATIVE_NEGATIVE1") (pintype "bidirectional"))
      (node (ref "U$55") (pin "POSITIVE") (pinfunction "POSITIVE_POSITIVE") (pintype "bidirectional"))
      (node (ref "U$55") (pin "POSITIVE1") (pinfunction "POSITIVE_POSITIVE1") (pintype "bidirectional"))
    )
    (net (code "45") (name "Net-(U$56-NEGATIVE-PadNEGATIVE1)") (class "Default")
      (node (ref "U$56") (pin "NEGATIVE") (pinfunction "NEGATIVE_NEGATIVE") (pintype "bidirectional"))
      (node (ref "U$56") (pin "NEGATIVE1") (pinfunction "NEGATIVE_NEGATIVE1") (pintype "bidirectional"))
      (node (ref "U$57") (pin "POSITIVE") (pinfunction "POSITIVE_POSITIVE") (pintype "bidirectional"))
      (node (ref "U$57") (pin "POSITIVE1") (pinfunction "POSITIVE_POSITIVE1") (pintype "bidirectional"))
    )
    (net (code "46") (name "Net-(U$57-NEGATIVE-PadNEGATIVE1)") (class "Default")
      (node (ref "U$57") (pin "NEGATIVE") (pinfunction "NEGATIVE_NEGATIVE") (pintype "bidirectional"))
      (node (ref "U$57") (pin "NEGATIVE1") (pinfunction "NEGATIVE_NEGATIVE1") (pintype "bidirectional"))
      (node (ref "U$58") (pin "POSITIVE") (pinfunction "POSITIVE_POSITIVE") (pintype "bidirectional"))
      (node (ref "U$58") (pin "POSITIVE1") (pinfunction "POSITIVE_POSITIVE1") (pintype "bidirectional"))
    )
    (net (code "47") (name "Net-(U$58-NEGATIVE-PadNEGATIVE1)") (class "Default")
      (node (ref "U$58") (pin "NEGATIVE") (pinfunction "NEGATIVE_NEGATIVE") (pintype "bidirectional"))
      (node (ref "U$58") (pin "NEGATIVE1") (pinfunction "NEGATIVE_NEGATIVE1") (pintype "bidirectional"))
      (node (ref "U$59") (pin "POSITIVE") (pinfunction "POSITIVE_POSITIVE") (pintype "bidirectional"))
      (node (ref "U$59") (pin "POSITIVE1") (pinfunction "POSITIVE_POSITIVE1") (pintype "bidirectional"))
    )
    (net (code "48") (name "Net-(U$59-NEGATIVE-PadNEGATIVE1)") (class "Default")
      (node (ref "U$59") (pin "NEGATIVE") (pinfunction "NEGATIVE_NEGATIVE") (pintype "bidirectional"))
      (node (ref "U$59") (pin "NEGATIVE1") (pinfunction "NEGATIVE_NEGATIVE1") (pintype "bidirectional"))
      (node (ref "U$60") (pin "POSITIVE") (pinfunction "POSITIVE_POSITIVE") (pintype "bidirectional"))
      (node (ref "U$60") (pin "POSITIVE1") (pinfunction "POSITIVE_POSITIVE1") (pintype "bidirectional"))
    )
    (net (code "49") (name "Net-(U$60-NEGATIVE-PadNEGATIVE1)") (class "Default")
      (node (ref "U$60") (pin "NEGATIVE") (pinfunction "NEGATIVE_NEGATIVE") (pintype "bidirectional"))
      (node (ref "U$60") (pin "NEGATIVE1") (pinfunction "NEGATIVE_NEGATIVE1") (pintype "bidirectional"))
      (node (ref "U$61") (pin "POSITIVE") (pinfunction "POSITIVE_POSITIVE") (pintype "bidirectional"))
      (node (ref "U$61") (pin "POSITIVE1") (pinfunction "POSITIVE_POSITIVE1") (pintype "bidirectional"))
    )
    (net (code "50") (name "Net-(U$61-NEGATIVE-PadNEGATIVE1)") (class "Default")
      (node (ref "U$61") (pin "NEGATIVE") (pinfunction "NEGATIVE_NEGATIVE") (pintype "bidirectional"))
      (node (ref "U$61") (pin "NEGATIVE1") (pinfunction "NEGATIVE_NEGATIVE1") (pintype "bidirectional"))
      (node (ref "U$62") (pin "POSITIVE") (pinfunction "POSITIVE_POSITIVE") (pintype "bidirectional"))
      (node (ref "U$62") (pin "POSITIVE1") (pinfunction "POSITIVE_POSITIVE1") (pintype "bidirectional"))
    )
    (net (code "51") (name "Net-(U$62-NEGATIVE-PadNEGATIVE1)") (class "Default")
      (node (ref "U$62") (pin "NEGATIVE") (pinfunction "NEGATIVE_NEGATIVE") (pintype "bidirectional"))
      (node (ref "U$62") (pin "NEGATIVE1") (pinfunction "NEGATIVE_NEGATIVE1") (pintype "bidirectional"))
      (node (ref "U$63") (pin "POSITIVE") (pinfunction "POSITIVE_POSITIVE") (pintype "bidirectional"))
      (node (ref "U$63") (pin "POSITIVE1") (pinfunction "POSITIVE_POSITIVE1") (pintype "bidirectional"))
    )
    (net (code "52") (name "Net-(U$63-NEGATIVE-PadNEGATIVE1)") (class "Default")
      (node (ref "U$63") (pin "NEGATIVE") (pinfunction "NEGATIVE_NEGATIVE") (pintype "bidirectional"))
      (node (ref "U$63") (pin "NEGATIVE1") (pinfunction "NEGATIVE_NEGATIVE1") (pintype "bidirectional"))
      (node (ref "U$64") (pin "POSITIVE") (pinfunction "POSITIVE_POSITIVE") (pintype "bidirectional"))
      (node (ref "U$64") (pin "POSITIVE1") (pinfunction "POSITIVE_POSITIVE1") (pintype "bidirectional"))
    )
    (net (code "53") (name "Net-(U$64-NEGATIVE-PadNEGATIVE1)") (class "Default")
      (node (ref "U$64") (pin "NEGATIVE") (pinfunction "NEGATIVE_NEGATIVE") (pintype "bidirectional"))
      (node (ref "U$64") (pin "NEGATIVE1") (pinfunction "NEGATIVE_NEGATIVE1") (pintype "bidirectional"))
      (node (ref "U$65") (pin "POSITIVE") (pinfunction "POSITIVE_POSITIVE") (pintype "bidirectional"))
      (node (ref "U$65") (pin "POSITIVE1") (pinfunction "POSITIVE_POSITIVE1") (pintype "bidirectional"))
    )
    (net (code "54") (name "Net-(U$66-NEGATIVE-PadNEGATIVE1)") (class "Default")
      (node (ref "U$66") (pin "NEGATIVE") (pinfunction "NEGATIVE_NEGATIVE") (pintype "bidirectional"))
      (node (ref "U$66") (pin "NEGATIVE1") (pinfunction "NEGATIVE_NEGATIVE1") (pintype "bidirectional"))
      (node (ref "U$67") (pin "POSITIVE") (pinfunction "POSITIVE_POSITIVE") (pintype "bidirectional"))
      (node (ref "U$67") (pin "POSITIVE1") (pinfunction "POSITIVE_POSITIVE1") (pintype "bidirectional"))
    )
    (net (code "55") (name "Net-(U$67-NEGATIVE-PadNEGATIVE1)") (class "Default")
      (node (ref "U$67") (pin "NEGATIVE") (pinfunction "NEGATIVE_NEGATIVE") (pintype "bidirectional"))
      (node (ref "U$67") (pin "NEGATIVE1") (pinfunction "NEGATIVE_NEGATIVE1") (pintype "bidirectional"))
      (node (ref "U$68") (pin "POSITIVE") (pinfunction "POSITIVE_POSITIVE") (pintype "bidirectional"))
      (node (ref "U$68") (pin "POSITIVE1") (pinfunction "POSITIVE_POSITIVE1") (pintype "bidirectional"))
    )
    (net (code "56") (name "Net-(U$68-NEGATIVE-PadNEGATIVE1)") (class "Default")
      (node (ref "U$68") (pin "NEGATIVE") (pinfunction "NEGATIVE_NEGATIVE") (pintype "bidirectional"))
      (node (ref "U$68") (pin "NEGATIVE1") (pinfunction "NEGATIVE_NEGATIVE1") (pintype "bidirectional"))
      (node (ref "U$69") (pin "POSITIVE") (pinfunction "POSITIVE_POSITIVE") (pintype "bidirectional"))
      (node (ref "U$69") (pin "POSITIVE1") (pinfunction "POSITIVE_POSITIVE1") (pintype "bidirectional"))
    )
    (net (code "57") (name "Net-(U$69-NEGATIVE-PadNEGATIVE1)") (class "Default")
      (node (ref "U$69") (pin "NEGATIVE") (pinfunction "NEGATIVE_NEGATIVE") (pintype "bidirectional"))
      (node (ref "U$69") (pin "NEGATIVE1") (pinfunction "NEGATIVE_NEGATIVE1") (pintype "bidirectional"))
      (node (ref "U$70") (pin "POSITIVE") (pinfunction "POSITIVE_POSITIVE") (pintype "bidirectional"))
      (node (ref "U$70") (pin "POSITIVE1") (pinfunction "POSITIVE_POSITIVE1") (pintype "bidirectional"))
    )
    (net (code "58") (name "Net-(U$70-NEGATIVE-PadNEGATIVE1)") (class "Default")
      (node (ref "U$70") (pin "NEGATIVE") (pinfunction "NEGATIVE_NEGATIVE") (pintype "bidirectional"))
      (node (ref "U$70") (pin "NEGATIVE1") (pinfunction "NEGATIVE_NEGATIVE1") (pintype "bidirectional"))
      (node (ref "U$71") (pin "POSITIVE") (pinfunction "POSITIVE_POSITIVE") (pintype "bidirectional"))
      (node (ref "U$71") (pin "POSITIVE1") (pinfunction "POSITIVE_POSITIVE1") (pintype "bidirectional"))
    )
    (net (code "59") (name "Net-(U$71-NEGATIVE-PadNEGATIVE1)") (class "Default")
      (node (ref "U$71") (pin "NEGATIVE") (pinfunction "NEGATIVE_NEGATIVE") (pintype "bidirectional"))
      (node (ref "U$71") (pin "NEGATIVE1") (pinfunction "NEGATIVE_NEGATIVE1") (pintype "bidirectional"))
      (node (ref "U$72") (pin "POSITIVE") (pinfunction "POSITIVE_POSITIVE") (pintype "bidirectional"))
      (node (ref "U$72") (pin "POSITIVE1") (pinfunction "POSITIVE_POSITIVE1") (pintype "bidirectional"))
    )
    (net (code "60") (name "Net-(U$72-NEGATIVE-PadNEGATIVE1)") (class "Default")
      (node (ref "U$72") (pin "NEGATIVE") (pinfunction "NEGATIVE_NEGATIVE") (pintype "bidirectional"))
      (node (ref "U$72") (pin "NEGATIVE1") (pinfunction "NEGATIVE_NEGATIVE1") (pintype "bidirectional"))
      (node (ref "U$73") (pin "POSITIVE") (pinfunction "POSITIVE_POSITIVE") (pintype "bidirectional"))
      (node (ref "U$73") (pin "POSITIVE1") (pinfunction "POSITIVE_POSITIVE1") (pintype "bidirectional"))
    )
    (net (code "61") (name "Net-(U$73-NEGATIVE-PadNEGATIVE1)") (class "Default")
      (node (ref "U$73") (pin "NEGATIVE") (pinfunction "NEGATIVE_NEGATIVE") (pintype "bidirectional"))
      (node (ref "U$73") (pin "NEGATIVE1") (pinfunction "NEGATIVE_NEGATIVE1") (pintype "bidirectional"))
      (node (ref "U$74") (pin "POSITIVE") (pinfunction "POSITIVE_POSITIVE") (pintype "bidirectional"))
      (node (ref "U$74") (pin "POSITIVE1") (pinfunction "POSITIVE_POSITIVE1") (pintype "bidirectional"))
    )
    (net (code "62") (name "Net-(U$74-NEGATIVE-PadNEGATIVE1)") (class "Default")
      (node (ref "U$74") (pin "NEGATIVE") (pinfunction "NEGATIVE_NEGATIVE") (pintype "bidirectional"))
      (node (ref "U$74") (pin "NEGATIVE1") (pinfunction "NEGATIVE_NEGATIVE1") (pintype "bidirectional"))
      (node (ref "U$75") (pin "POSITIVE") (pinfunction "POSITIVE_POSITIVE") (pintype "bidirectional"))
      (node (ref "U$75") (pin "POSITIVE1") (pinfunction "POSITIVE_POSITIVE1") (pintype "bidirectional"))
    )
    (net (code "63") (name "unconnected-(U$16-PadTHERMAL)") (class "Default")
      (node (ref "U$16") (pin "THERMAL") (pinfunction "THERMAL_THERMAL") (pintype "bidirectional"))
    )
    (net (code "64") (name "unconnected-(U$17-PadTHERMAL)") (class "Default")
      (node (ref "U$17") (pin "THERMAL") (pinfunction "THERMAL_THERMAL") (pintype "bidirectional"))
    )
    (net (code "65") (name "unconnected-(U$18-PadTHERMAL)") (class "Default")
      (node (ref "U$18") (pin "THERMAL") (pinfunction "THERMAL_THERMAL") (pintype "bidirectional"))
    )
    (net (code "66") (name "unconnected-(U$19-PadTHERMAL)") (class "Default")
      (node (ref "U$19") (pin "THERMAL") (pinfunction "THERMAL_THERMAL") (pintype "bidirectional"))
    )
    (net (code "67") (name "unconnected-(U$20-PadTHERMAL)") (class "Default")
      (node (ref "U$20") (pin "THERMAL") (pinfunction "THERMAL_THERMAL") (pintype "bidirectional"))
    )
    (net (code "68") (name "unconnected-(U$21-PadTHERMAL)") (class "Default")
      (node (ref "U$21") (pin "THERMAL") (pinfunction "THERMAL_THERMAL") (pintype "bidirectional"))
    )
    (net (code "69") (name "unconnected-(U$22-PadTHERMAL)") (class "Default")
      (node (ref "U$22") (pin "THERMAL") (pinfunction "THERMAL_THERMAL") (pintype "bidirectional"))
    )
    (net (code "70") (name "unconnected-(U$23-PadTHERMAL)") (class "Default")
      (node (ref "U$23") (pin "THERMAL") (pinfunction "THERMAL_THERMAL") (pintype "bidirectional"))
    )
    (net (code "71") (name "unconnected-(U$24-PadTHERMAL)") (class "Default")
      (node (ref "U$24") (pin "THERMAL") (pinfunction "THERMAL_THERMAL") (pintype "bidirectional"))
    )
    (net (code "72") (name "unconnected-(U$25-PadTHERMAL)") (class "Default")
      (node (ref "U$25") (pin "THERMAL") (pinfunction "THERMAL_THERMAL") (pintype "bidirectional"))
    )
    (net (code "73") (name "unconnected-(U$26-PadTHERMAL)") (class "Default")
      (node (ref "U$26") (pin "THERMAL") (pinfunction "THERMAL_THERMAL") (pintype "bidirectional"))
    )
    (net (code "74") (name "unconnected-(U$27-PadTHERMAL)") (class "Default")
      (node (ref "U$27") (pin "THERMAL") (pinfunction "THERMAL_THERMAL") (pintype "bidirectional"))
    )
    (net (code "75") (name "unconnected-(U$28-PadTHERMAL)") (class "Default")
      (node (ref "U$28") (pin "THERMAL") (pinfunction "THERMAL_THERMAL") (pintype "bidirectional"))
    )
    (net (code "76") (name "unconnected-(U$29-PadTHERMAL)") (class "Default")
      (node (ref "U$29") (pin "THERMAL") (pinfunction "THERMAL_THERMAL") (pintype "bidirectional"))
    )
    (net (code "77") (name "unconnected-(U$30-PadTHERMAL)") (class "Default")
      (node (ref "U$30") (pin "THERMAL") (pinfunction "THERMAL_THERMAL") (pintype "bidirectional"))
    )
    (net (code "78") (name "unconnected-(U$31-PadTHERMAL)") (class "Default")
      (node (ref "U$31") (pin "THERMAL") (pinfunction "THERMAL_THERMAL") (pintype "bidirectional"))
    )
    (net (code "79") (name "unconnected-(U$32-PadTHERMAL)") (class "Default")
      (node (ref "U$32") (pin "THERMAL") (pinfunction "THERMAL_THERMAL") (pintype "bidirectional"))
    )
    (net (code "80") (name "unconnected-(U$33-PadTHERMAL)") (class "Default")
      (node (ref "U$33") (pin "THERMAL") (pinfunction "THERMAL_THERMAL") (pintype "bidirectional"))
    )
    (net (code "81") (name "unconnected-(U$34-PadTHERMAL)") (class "Default")
      (node (ref "U$34") (pin "THERMAL") (pinfunction "THERMAL_THERMAL") (pintype "bidirectional"))
    )
    (net (code "82") (name "unconnected-(U$35-PadTHERMAL)") (class "Default")
      (node (ref "U$35") (pin "THERMAL") (pinfunction "THERMAL_THERMAL") (pintype "bidirectional"))
    )
    (net (code "83") (name "unconnected-(U$36-PadTHERMAL)") (class "Default")
      (node (ref "U$36") (pin "THERMAL") (pinfunction "THERMAL_THERMAL") (pintype "bidirectional"))
    )
    (net (code "84") (name "unconnected-(U$37-PadTHERMAL)") (class "Default")
      (node (ref "U$37") (pin "THERMAL") (pinfunction "THERMAL_THERMAL") (pintype "bidirectional"))
    )
    (net (code "85") (name "unconnected-(U$38-PadTHERMAL)") (class "Default")
      (node (ref "U$38") (pin "THERMAL") (pinfunction "THERMAL_THERMAL") (pintype "bidirectional"))
    )
    (net (code "86") (name "unconnected-(U$39-PadTHERMAL)") (class "Default")
      (node (ref "U$39") (pin "THERMAL") (pinfunction "THERMAL_THERMAL") (pintype "bidirectional"))
    )
    (net (code "87") (name "unconnected-(U$40-PadTHERMAL)") (class "Default")
      (node (ref "U$40") (pin "THERMAL") (pinfunction "THERMAL_THERMAL") (pintype "bidirectional"))
    )
    (net (code "88") (name "unconnected-(U$41-PadTHERMAL)") (class "Default")
      (node (ref "U$41") (pin "THERMAL") (pinfunction "THERMAL_THERMAL") (pintype "bidirectional"))
    )
    (net (code "89") (name "unconnected-(U$42-PadTHERMAL)") (class "Default")
      (node (ref "U$42") (pin "THERMAL") (pinfunction "THERMAL_THERMAL") (pintype "bidirectional"))
    )
    (net (code "90") (name "unconnected-(U$43-PadTHERMAL)") (class "Default")
      (node (ref "U$43") (pin "THERMAL") (pinfunction "THERMAL_THERMAL") (pintype "bidirectional"))
    )
    (net (code "91") (name "unconnected-(U$44-PadTHERMAL)") (class "Default")
      (node (ref "U$44") (pin "THERMAL") (pinfunction "THERMAL_THERMAL") (pintype "bidirectional"))
    )
    (net (code "92") (name "unconnected-(U$45-PadTHERMAL)") (class "Default")
      (node (ref "U$45") (pin "THERMAL") (pinfunction "THERMAL_THERMAL") (pintype "bidirectional"))
    )
    (net (code "93") (name "unconnected-(U$46-PadTHERMAL)") (class "Default")
      (node (ref "U$46") (pin "THERMAL") (pinfunction "THERMAL_THERMAL") (pintype "bidirectional"))
    )
    (net (code "94") (name "unconnected-(U$47-PadTHERMAL)") (class "Default")
      (node (ref "U$47") (pin "THERMAL") (pinfunction "THERMAL_THERMAL") (pintype "bidirectional"))
    )
    (net (code "95") (name "unconnected-(U$48-PadTHERMAL)") (class "Default")
      (node (ref "U$48") (pin "THERMAL") (pinfunction "THERMAL_THERMAL") (pintype "bidirectional"))
    )
    (net (code "96") (name "unconnected-(U$49-PadTHERMAL)") (class "Default")
      (node (ref "U$49") (pin "THERMAL") (pinfunction "THERMAL_THERMAL") (pintype "bidirectional"))
    )
    (net (code "97") (name "unconnected-(U$50-PadTHERMAL)") (class "Default")
      (node (ref "U$50") (pin "THERMAL") (pinfunction "THERMAL_THERMAL") (pintype "bidirectional"))
    )
    (net (code "98") (name "unconnected-(U$51-PadTHERMAL)") (class "Default")
      (node (ref "U$51") (pin "THERMAL") (pinfunction "THERMAL_THERMAL") (pintype "bidirectional"))
    )
    (net (code "99") (name "unconnected-(U$52-PadTHERMAL)") (class "Default")
      (node (ref "U$52") (pin "THERMAL") (pinfunction "THERMAL_THERMAL") (pintype "bidirectional"))
    )
    (net (code "100") (name "unconnected-(U$53-PadTHERMAL)") (class "Default")
      (node (ref "U$53") (pin "THERMAL") (pinfunction "THERMAL_THERMAL") (pintype "bidirectional"))
    )
    (net (code "101") (name "unconnected-(U$54-PadTHERMAL)") (class "Default")
      (node (ref "U$54") (pin "THERMAL") (pinfunction "THERMAL_THERMAL") (pintype "bidirectional"))
    )
    (net (code "102") (name "unconnected-(U$55-PadTHERMAL)") (class "Default")
      (node (ref "U$55") (pin "THERMAL") (pinfunction "THERMAL_THERMAL") (pintype "bidirectional"))
    )
    (net (code "103") (name "unconnected-(U$56-PadTHERMAL)") (class "Default")
      (node (ref "U$56") (pin "THERMAL") (pinfunction "THERMAL_THERMAL") (pintype "bidirectional"))
    )
    (net (code "104") (name "unconnected-(U$57-PadTHERMAL)") (class "Default")
      (node (ref "U$57") (pin "THERMAL") (pinfunction "THERMAL_THERMAL") (pintype "bidirectional"))
    )
    (net (code "105") (name "unconnected-(U$58-PadTHERMAL)") (class "Default")
      (node (ref "U$58") (pin "THERMAL") (pinfunction "THERMAL_THERMAL") (pintype "bidirectional"))
    )
    (net (code "106") (name "unconnected-(U$59-PadTHERMAL)") (class "Default")
      (node (ref "U$59") (pin "THERMAL") (pinfunction "THERMAL_THERMAL") (pintype "bidirectional"))
    )
    (net (code "107") (name "unconnected-(U$60-PadTHERMAL)") (class "Default")
      (node (ref "U$60") (pin "THERMAL") (pinfunction "THERMAL_THERMAL") (pintype "bidirectional"))
    )
    (net (code "108") (name "unconnected-(U$61-PadTHERMAL)") (class "Default")
      (node (ref "U$61") (pin "THERMAL") (pinfunction "THERMAL_THERMAL") (pintype "bidirectional"))
    )
    (net (code "109") (name "unconnected-(U$62-PadTHERMAL)") (class "Default")
      (node (ref "U$62") (pin "THERMAL") (pinfunction "THERMAL_THERMAL") (pintype "bidirectional"))
    )
    (net (code "110") (name "unconnected-(U$63-PadTHERMAL)") (class "Default")
      (node (ref "U$63") (pin "THERMAL") (pinfunction "THERMAL_THERMAL") (pintype "bidirectional"))
    )
    (net (code "111") (name "unconnected-(U$64-PadTHERMAL)") (class "Default")
      (node (ref "U$64") (pin "THERMAL") (pinfunction "THERMAL_THERMAL") (pintype "bidirectional"))
    )
    (net (code "112") (name "unconnected-(U$65-PadTHERMAL)") (class "Default")
      (node (ref "U$65") (pin "THERMAL") (pinfunction "THERMAL_THERMAL") (pintype "bidirectional"))
    )
    (net (code "113") (name "unconnected-(U$66-PadTHERMAL)") (class "Default")
      (node (ref "U$66") (pin "THERMAL") (pinfunction "THERMAL_THERMAL") (pintype "bidirectional"))
    )
    (net (code "114") (name "unconnected-(U$67-PadTHERMAL)") (class "Default")
      (node (ref "U$67") (pin "THERMAL") (pinfunction "THERMAL_THERMAL") (pintype "bidirectional"))
    )
    (net (code "115") (name "unconnected-(U$68-PadTHERMAL)") (class "Default")
      (node (ref "U$68") (pin "THERMAL") (pinfunction "THERMAL_THERMAL") (pintype "bidirectional"))
    )
    (net (code "116") (name "unconnected-(U$69-PadTHERMAL)") (class "Default")
      (node (ref "U$69") (pin "THERMAL") (pinfunction "THERMAL_THERMAL") (pintype "bidirectional"))
    )
    (net (code "117") (name "unconnected-(U$70-PadTHERMAL)") (class "Default")
      (node (ref "U$70") (pin "THERMAL") (pinfunction "THERMAL_THERMAL") (pintype "bidirectional"))
    )
    (net (code "118") (name "unconnected-(U$71-PadTHERMAL)") (class "Default")
      (node (ref "U$71") (pin "THERMAL") (pinfunction "THERMAL_THERMAL") (pintype "bidirectional"))
    )
    (net (code "119") (name "unconnected-(U$72-PadTHERMAL)") (class "Default")
      (node (ref "U$72") (pin "THERMAL") (pinfunction "THERMAL_THERMAL") (pintype "bidirectional"))
    )
    (net (code "120") (name "unconnected-(U$73-PadTHERMAL)") (class "Default")
      (node (ref "U$73") (pin "THERMAL") (pinfunction "THERMAL_THERMAL") (pintype "bidirectional"))
    )
    (net (code "121") (name "unconnected-(U$74-PadTHERMAL)") (class "Default")
      (node (ref "U$74") (pin "THERMAL") (pinfunction "THERMAL_THERMAL") (pintype "bidirectional"))
    )
    (net (code "122") (name "unconnected-(U$75-PadTHERMAL)") (class "Default")
      (node (ref "U$75") (pin "THERMAL") (pinfunction "THERMAL_THERMAL") (pintype "bidirectional"))
    )
  )
)
